# HEBoard_ver4.net
KiCad netlist of a schematic drawn in Altium Designer
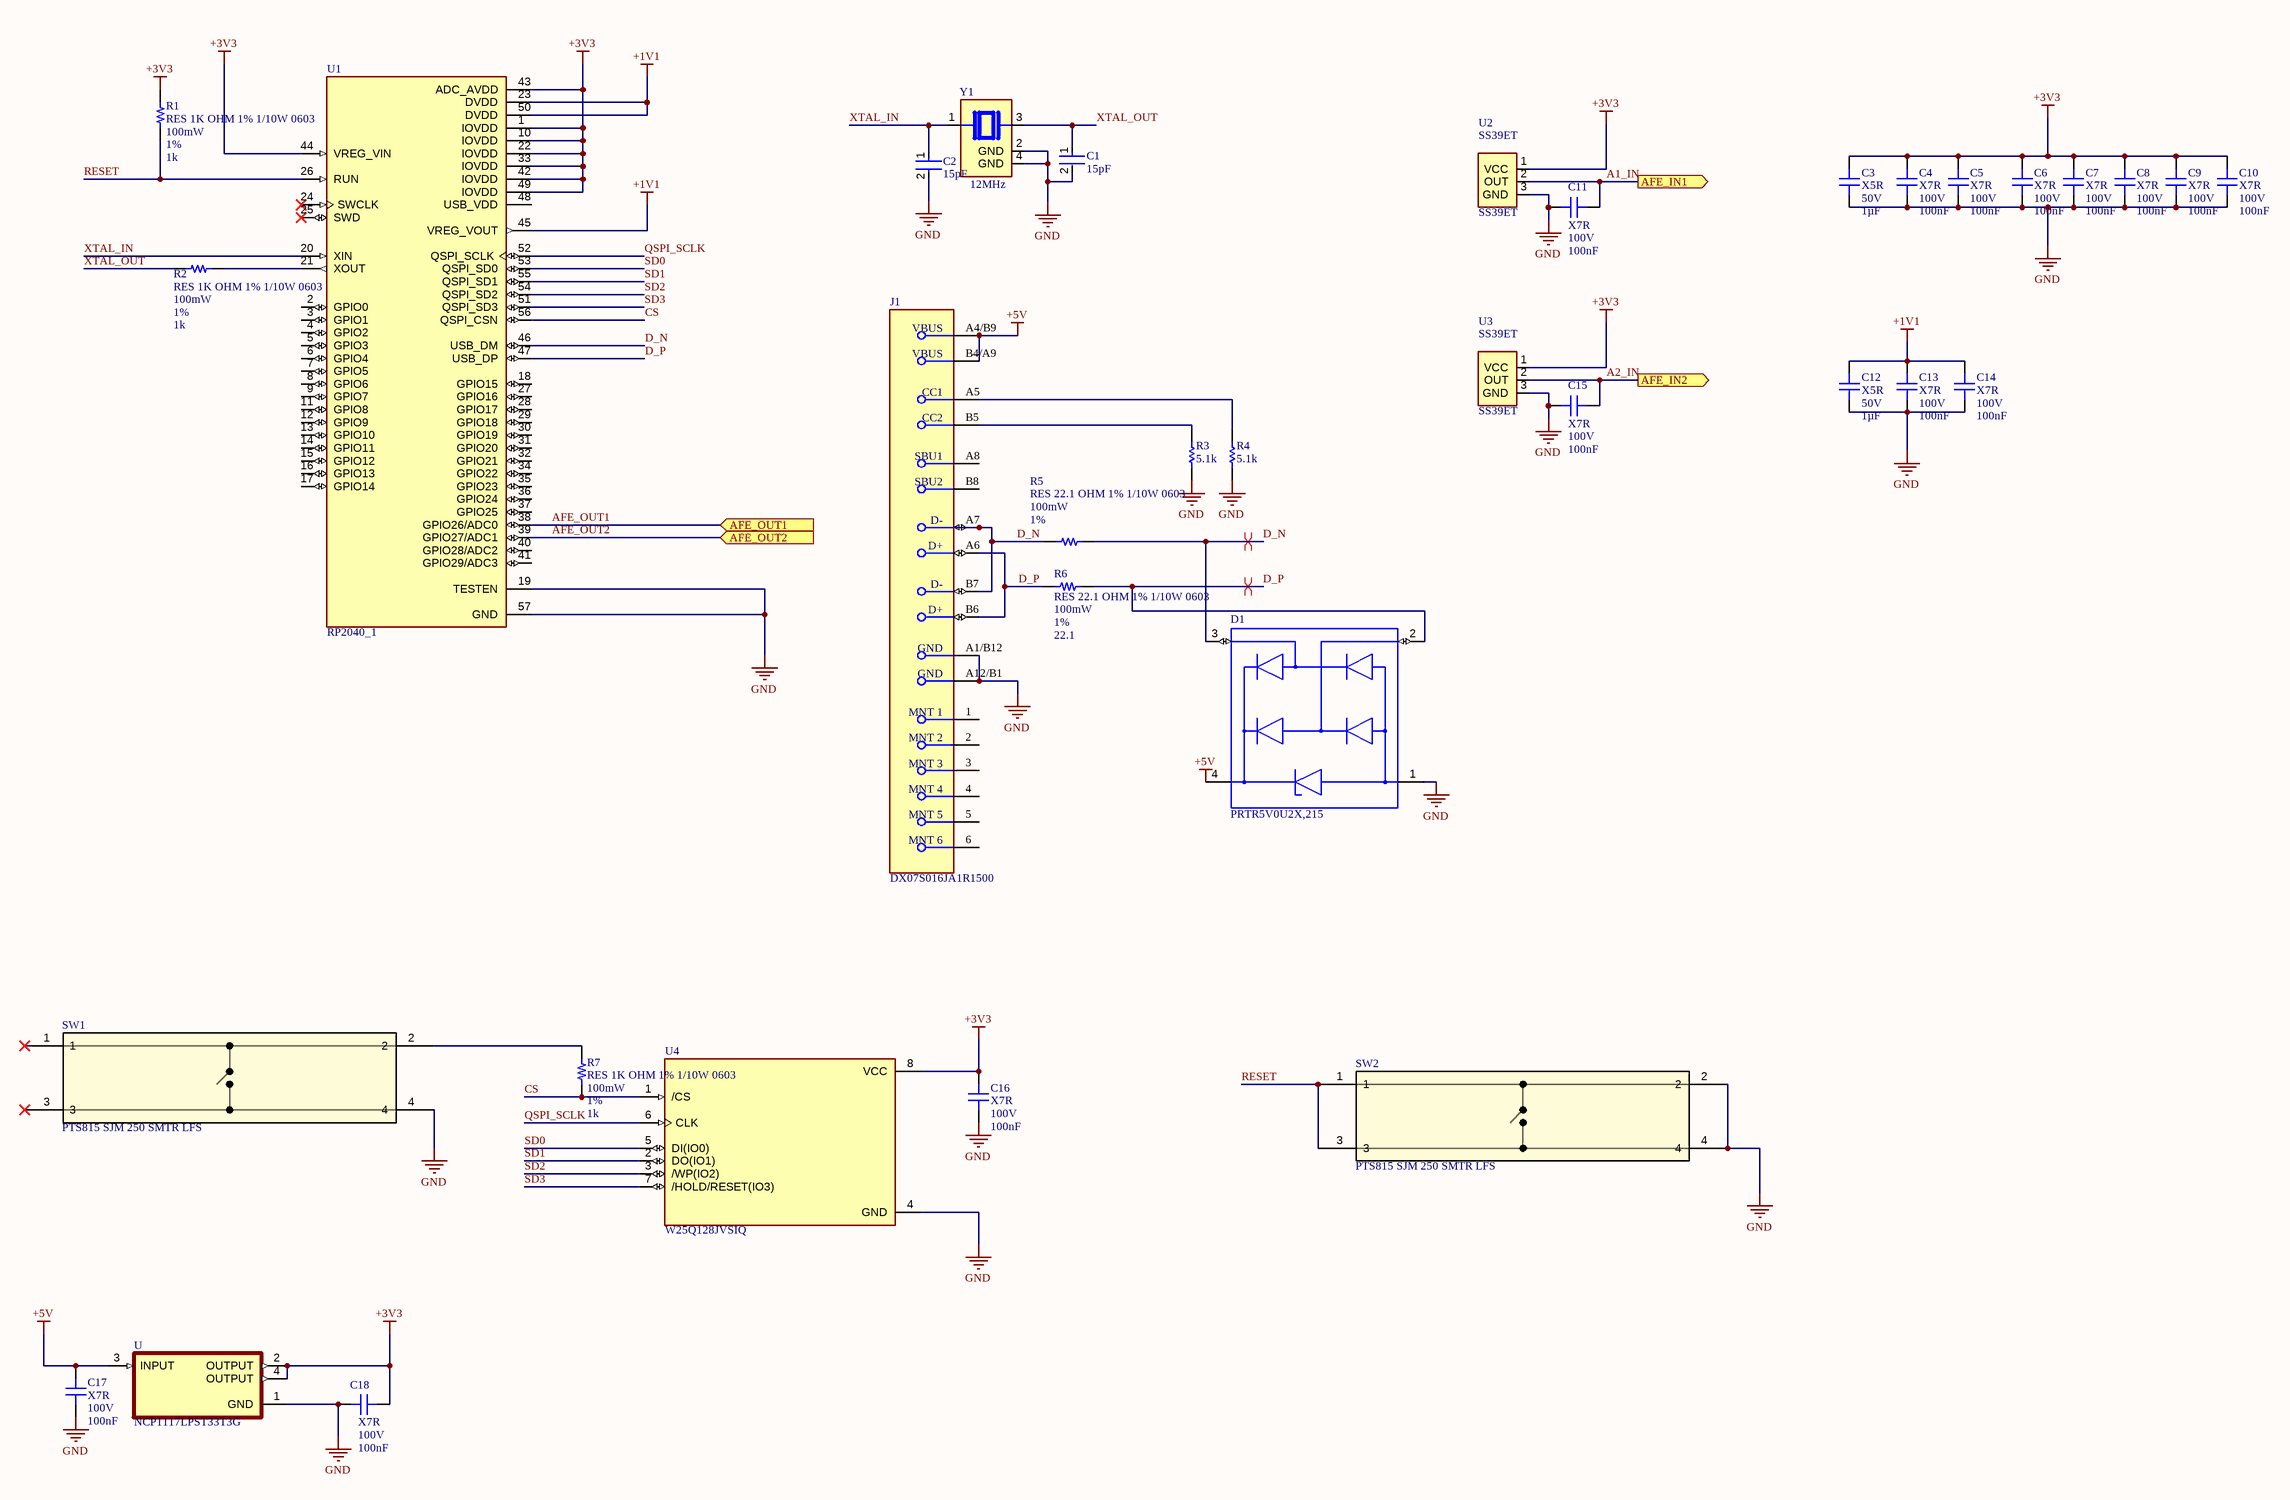
[diagram p0: HEBoard_ver4.SchDoc]

(export (version "E")
  (design (tool "Eeschema 10.0.6"))
  (components
    (comp (ref "C1")
      (value "15pF")
      (footprint "FP-CC0603-0_9-MFG")
      (description "CAP CER 15PF 50V C0G/NPO 0603")
      (fields (field (name "TOLERANCE") "5%"))
      (libsource (lib "Altium Content Vault") (part "11868f565c42a9108669ba33697ecf6"))
    )
    (comp (ref "C2")
      (value "15pF")
      (footprint "FP-CC0603-0_9-MFG")
      (description "CAP CER 15PF 50V C0G/NPO 0603")
      (fields (field (name "TOLERANCE") "5%"))
      (libsource (lib "Altium Content Vault") (part "11868f565c42a9108669ba33697ecf6"))
    )
    (comp (ref "C3")
      (value "CAP CER 1UF 50V X5R 0603")
      (footprint "CAP 0603_1608")
      (description "1µF ±10% 50V Ceramic Capacitor X7R 0603 (1608 Metric)")
      (fields
        (field (name "DIELECTRIC CODE") "X5R")
        (field (name "VOLTAGE RATING") "50V")
        (field (name "CAPACITANCE") "1µF")
        (field (name "TOLERANCE") "10%")
      )
      (libsource (lib "Midnight Sun") (part "Capacitor"))
    )
    (comp (ref "C4")
      (value "CAP CER 0.1UF 100V 10% X7R 0603")
      (footprint "CAP 0603_1608")
      (fields
        (field (name "DIELECTRIC CODE") "X7R")
        (field (name "VOLTAGE RATING") "100V")
        (field (name "CAPACITANCE") "100nF")
        (field (name "TOLERANCE") "10%")
      )
      (libsource (lib "Midnight Sun") (part "Capacitor"))
    )
    (comp (ref "C5")
      (value "CAP CER 0.1UF 100V 10% X7R 0603")
      (footprint "CAP 0603_1608")
      (fields
        (field (name "DIELECTRIC CODE") "X7R")
        (field (name "VOLTAGE RATING") "100V")
        (field (name "CAPACITANCE") "100nF")
        (field (name "TOLERANCE") "10%")
      )
      (libsource (lib "Midnight Sun") (part "Capacitor"))
    )
    (comp (ref "C6")
      (value "CAP CER 0.1UF 100V 10% X7R 0603")
      (footprint "CAP 0603_1608")
      (fields
        (field (name "DIELECTRIC CODE") "X7R")
        (field (name "VOLTAGE RATING") "100V")
        (field (name "CAPACITANCE") "100nF")
        (field (name "TOLERANCE") "10%")
      )
      (libsource (lib "Midnight Sun") (part "Capacitor"))
    )
    (comp (ref "C7")
      (value "CAP CER 0.1UF 100V 10% X7R 0603")
      (footprint "CAP 0603_1608")
      (fields
        (field (name "DIELECTRIC CODE") "X7R")
        (field (name "VOLTAGE RATING") "100V")
        (field (name "CAPACITANCE") "100nF")
        (field (name "TOLERANCE") "10%")
      )
      (libsource (lib "Midnight Sun") (part "Capacitor"))
    )
    (comp (ref "C8")
      (value "CAP CER 0.1UF 100V 10% X7R 0603")
      (footprint "CAP 0603_1608")
      (fields
        (field (name "DIELECTRIC CODE") "X7R")
        (field (name "VOLTAGE RATING") "100V")
        (field (name "CAPACITANCE") "100nF")
        (field (name "TOLERANCE") "10%")
      )
      (libsource (lib "Midnight Sun") (part "Capacitor"))
    )
    (comp (ref "C9")
      (value "CAP CER 0.1UF 100V 10% X7R 0603")
      (footprint "CAP 0603_1608")
      (fields
        (field (name "DIELECTRIC CODE") "X7R")
        (field (name "VOLTAGE RATING") "100V")
        (field (name "CAPACITANCE") "100nF")
        (field (name "TOLERANCE") "10%")
      )
      (libsource (lib "Midnight Sun") (part "Capacitor"))
    )
    (comp (ref "C10")
      (value "CAP CER 0.1UF 100V 10% X7R 0603")
      (footprint "CAP 0603_1608")
      (fields
        (field (name "DIELECTRIC CODE") "X7R")
        (field (name "VOLTAGE RATING") "100V")
        (field (name "CAPACITANCE") "100nF")
        (field (name "TOLERANCE") "10%")
      )
      (libsource (lib "Midnight Sun") (part "Capacitor"))
    )
    (comp (ref "C11")
      (value "CAP CER 0.1UF 100V 10% X7R 0603")
      (footprint "CAP 0603_1608")
      (fields
        (field (name "DIELECTRIC CODE") "X7R")
        (field (name "VOLTAGE RATING") "100V")
        (field (name "CAPACITANCE") "100nF")
        (field (name "TOLERANCE") "10%")
      )
      (libsource (lib "Midnight Sun") (part "Capacitor"))
    )
    (comp (ref "C12")
      (value "CAP CER 1UF 50V X5R 0603")
      (footprint "CAP 0603_1608")
      (description "1µF ±10% 50V Ceramic Capacitor X7R 0603 (1608 Metric)")
      (fields
        (field (name "DIELECTRIC CODE") "X5R")
        (field (name "VOLTAGE RATING") "50V")
        (field (name "CAPACITANCE") "1µF")
        (field (name "TOLERANCE") "10%")
      )
      (libsource (lib "Midnight Sun") (part "Capacitor"))
    )
    (comp (ref "C13")
      (value "CAP CER 0.1UF 100V 10% X7R 0603")
      (footprint "CAP 0603_1608")
      (fields
        (field (name "DIELECTRIC CODE") "X7R")
        (field (name "VOLTAGE RATING") "100V")
        (field (name "CAPACITANCE") "100nF")
        (field (name "TOLERANCE") "10%")
      )
      (libsource (lib "Midnight Sun") (part "Capacitor"))
    )
    (comp (ref "C14")
      (value "CAP CER 0.1UF 100V 10% X7R 0603")
      (footprint "CAP 0603_1608")
      (fields
        (field (name "DIELECTRIC CODE") "X7R")
        (field (name "VOLTAGE RATING") "100V")
        (field (name "CAPACITANCE") "100nF")
        (field (name "TOLERANCE") "10%")
      )
      (libsource (lib "Midnight Sun") (part "Capacitor"))
    )
    (comp (ref "C15")
      (value "CAP CER 0.1UF 100V 10% X7R 0603")
      (footprint "CAP 0603_1608")
      (fields
        (field (name "DIELECTRIC CODE") "X7R")
        (field (name "VOLTAGE RATING") "100V")
        (field (name "CAPACITANCE") "100nF")
        (field (name "TOLERANCE") "10%")
      )
      (libsource (lib "Midnight Sun") (part "Capacitor"))
    )
    (comp (ref "C16")
      (value "CAP CER 0.1UF 100V 10% X7R 0603")
      (footprint "CAP 0603_1608")
      (fields
        (field (name "DIELECTRIC CODE") "X7R")
        (field (name "VOLTAGE RATING") "100V")
        (field (name "CAPACITANCE") "100nF")
        (field (name "TOLERANCE") "10%")
      )
      (libsource (lib "Midnight Sun") (part "Capacitor"))
    )
    (comp (ref "C17")
      (value "CAP CER 0.1UF 100V 10% X7R 0603")
      (footprint "CAP 0603_1608")
      (fields
        (field (name "DIELECTRIC CODE") "X7R")
        (field (name "VOLTAGE RATING") "100V")
        (field (name "CAPACITANCE") "100nF")
        (field (name "TOLERANCE") "10%")
      )
      (libsource (lib "Midnight Sun") (part "Capacitor"))
    )
    (comp (ref "C18")
      (value "CAP CER 0.1UF 100V 10% X7R 0603")
      (footprint "CAP 0603_1608")
      (fields
        (field (name "DIELECTRIC CODE") "X7R")
        (field (name "VOLTAGE RATING") "100V")
        (field (name "CAPACITANCE") "100nF")
        (field (name "TOLERANCE") "10%")
      )
      (libsource (lib "Midnight Sun") (part "Capacitor"))
    )
    (comp (ref "D1")
      (value "PRTR5V0U2X,215")
      (footprint "FP-SOT143B-MFG")
      (description "TVS DIODE 5.5V SOT143B")
      (libsource (lib "Altium Content Vault") (part "31e4fa1655694efd507c8a671e666ef"))
    )
    (comp (ref "J1")
      (value "DX07S016JA1R1500")
      (footprint "FP-DX07S016JA1R1500-MFG")
      (description "CONN RCP USB2.0 TYP C 24P SMD RA")
      (libsource (lib "Altium Content Vault") (part "7f3e9989102a0f22bff9cb010881d34"))
    )
    (comp (ref "R1")
      (value "RES 1K OHM 1% 1/10W 0603")
      (footprint "RES 0603_1608")
      (description "1 kOhms ±1% 0.1W, 1/10W Chip Resistor 0603 (1608 Metric) Moisture Resistant Thick Film")
      (fields
        (field (name "POWER RATING") "100mW")
        (field (name "TOLERANCE") "1%")
        (field (name "RESISTANCE") "1k")
      )
      (libsource (lib "Midnight Sun") (part "Resistor"))
    )
    (comp (ref "R2")
      (value "RES 1K OHM 1% 1/10W 0603")
      (footprint "RES 0603_1608")
      (description "1 kOhms ±1% 0.1W, 1/10W Chip Resistor 0603 (1608 Metric) Moisture Resistant Thick Film")
      (fields
        (field (name "POWER RATING") "100mW")
        (field (name "TOLERANCE") "1%")
        (field (name "RESISTANCE") "1k")
      )
      (libsource (lib "Midnight Sun") (part "Resistor"))
    )
    (comp (ref "R3")
      (value "5.1k")
      (footprint "RESC1005X40X25NL05T10")
      (fields (field (name "PART NUMBER") "RC0402FR-075K1L") (field (name "MANUFACTURER") "Yageo / Phycomp"))
      (libsource (lib "Altium Content Vault") (part "RES"))
    )
    (comp (ref "R4")
      (value "5.1k")
      (footprint "RESC1005X40X25NL05T10")
      (fields (field (name "PART NUMBER") "RC0402FR-075K1L") (field (name "MANUFACTURER") "Yageo / Phycomp"))
      (libsource (lib "Altium Content Vault") (part "RES"))
    )
    (comp (ref "R5")
      (value "RES 22.1 OHM 1% 1/10W 0603")
      (footprint "RES 0603_1608")
      (fields (field (name "POWER RATING") "100mW") (field (name "TOLERANCE") "1%"))
      (libsource (lib "Midnight Sun") (part "Resistor"))
    )
    (comp (ref "R6")
      (value "RES 22.1 OHM 1% 1/10W 0603")
      (footprint "RES 0603_1608")
      (fields
        (field (name "POWER RATING") "100mW")
        (field (name "TOLERANCE") "1%")
        (field (name "RESISTANCE") "22.1")
      )
      (libsource (lib "Midnight Sun") (part "Resistor"))
    )
    (comp (ref "R7")
      (value "RES 1K OHM 1% 1/10W 0603")
      (footprint "RES 0603_1608")
      (description "1 kOhms ±1% 0.1W, 1/10W Chip Resistor 0603 (1608 Metric) Moisture Resistant Thick Film")
      (fields
        (field (name "POWER RATING") "100mW")
        (field (name "TOLERANCE") "1%")
        (field (name "RESISTANCE") "1k")
      )
      (libsource (lib "Midnight Sun") (part "Resistor"))
    )
    (comp (ref "SW1")
      (value "PTS815 SJM 250 SMTR LFS")
      (footprint "SW4_PTS815 SJM 250 SMTR LFS_CNK")
      (description "No Description Available")
      (libsource (lib "HEBoard_ver4") (part "PTS815 SJM 250 SMTR LFS"))
    )
    (comp (ref "SW2")
      (value "PTS815 SJM 250 SMTR LFS")
      (footprint "SW4_PTS815 SJM 250 SMTR LFS_CNK")
      (description "No Description Available")
      (libsource (lib "HEBoard_ver4") (part "PTS815 SJM 250 SMTR LFS"))
    )
    (comp (ref "U")
      (value "NCP1117LPST33T3G")
      (footprint "SnapEDApcb:SOT230P700X175-4N")
      (description "Linear Voltage Regulator IC 1 Output 1A SOT-223")
      (fields (field (name "MF") "ON Semiconductor"))
      (libsource (lib "HEBoard_ver4") (part "NCP1117LPST33T3G"))
    )
    (comp (ref "U1")
      (value "RP2040_1")
      (footprint "QFN40P700X700X90-57N")
      (description "RP2040 chip for Raspberry Pi Pico - ARMÂ® CortexÂ®-M0+ MCU 32-Bit")
      (fields (field (name "MP") "RP2040") (field (name "MF") "Raspberry Pi"))
      (libsource (lib "HEBoard_ver4") (part "RP2040_1"))
    )
    (comp (ref "U2")
      (value "SS39ET")
      (footprint "CHRY-MX1A-11NW_V")
      (description "analog Hall Effect Sensor 1.5 mA 2.7 - 6.5 V dc ¦ Honeywell SS39ET")
      (fields (field (name "MF") "Honeywell Sensing and Productivity Solutions"))
      (libsource (lib "HEBoard_ver4") (part "SS39ET"))
    )
    (comp (ref "U3")
      (value "SS39ET")
      (footprint "CHRY-MX1A-11NW_V")
      (description "analog Hall Effect Sensor 1.5 mA 2.7 - 6.5 V dc ¦ Honeywell SS39ET")
      (fields (field (name "MF") "Honeywell Sensing and Productivity Solutions"))
      (libsource (lib "HEBoard_ver4") (part "SS39ET"))
    )
    (comp (ref "U4")
      (value "W25Q128JVSIQ")
      (footprint "SOIC127P790X216-8N:SOIC127P790X216-8N")
      (description "FLASH - NOR Memory IC 128Mb (16M x 8) SPI - Quad I/O, QPI, DTR 133 MHz 8-SOIC")
      (fields (field (name "MF") "Winbond Electronics"))
      (libsource (lib "HEBoard_ver4") (part "W25Q128JVSIQ"))
    )
    (comp (ref "Y1")
      (value "12MHz")
      (footprint "XTAL_ABM8G-12.000MHZ-4Y-T3")
      (description "12 MHz Â±30ppm Crystal 10pF 120 Ohms 4-SMD, No Lead")
      (fields (field (name "MF") "Abracon") (field (name "MP") "ABM8G-12.000MHZ-4Y-T3"))
      (libsource (lib "HEBoard_ver4") (part "ABM8G-12.000MHZ-4Y-T3"))
    )
  )
  (nets
    (net (code "1") (name "+1V1") (class "Default")
      (node (ref "C12") (pin "2") (pinfunction "2_2") (pintype "passive"))
      (node (ref "C13") (pin "2") (pinfunction "2_2") (pintype "passive"))
      (node (ref "C14") (pin "2") (pinfunction "2_2") (pintype "passive"))
      (node (ref "U1") (pin "23") (pinfunction "DVDD_23") (pintype "power_in"))
      (node (ref "U1") (pin "45") (pinfunction "VREG_VOUT_45") (pintype "output"))
      (node (ref "U1") (pin "50") (pinfunction "DVDD_50") (pintype "power_in"))
    )
    (net (code "2") (name "+3V3") (class "Default")
      (node (ref "C10") (pin "2") (pinfunction "2_2") (pintype "passive"))
      (node (ref "C16") (pin "2") (pinfunction "2_2") (pintype "passive"))
      (node (ref "C18") (pin "1") (pinfunction "1_1") (pintype "passive"))
      (node (ref "C3") (pin "2") (pinfunction "2_2") (pintype "passive"))
      (node (ref "C4") (pin "2") (pinfunction "2_2") (pintype "passive"))
      (node (ref "C5") (pin "2") (pinfunction "2_2") (pintype "passive"))
      (node (ref "C6") (pin "2") (pinfunction "2_2") (pintype "passive"))
      (node (ref "C7") (pin "2") (pinfunction "2_2") (pintype "passive"))
      (node (ref "C8") (pin "2") (pinfunction "2_2") (pintype "passive"))
      (node (ref "C9") (pin "2") (pinfunction "2_2") (pintype "passive"))
      (node (ref "R1") (pin "2") (pinfunction "2_2") (pintype "passive"))
      (node (ref "U") (pin "2") (pinfunction "OUTPUT_2") (pintype "output"))
      (node (ref "U") (pin "4") (pinfunction "OUTPUT_4") (pintype "output"))
      (node (ref "U1") (pin "1") (pinfunction "IOVDD_1") (pintype "power_in"))
      (node (ref "U1") (pin "10") (pinfunction "IOVDD_10") (pintype "power_in"))
      (node (ref "U1") (pin "22") (pinfunction "IOVDD_22") (pintype "power_in"))
      (node (ref "U1") (pin "33") (pinfunction "IOVDD_33") (pintype "power_in"))
      (node (ref "U1") (pin "42") (pinfunction "IOVDD_42") (pintype "power_in"))
      (node (ref "U1") (pin "43") (pinfunction "ADC_AVDD_43") (pintype "power_in"))
      (node (ref "U1") (pin "44") (pinfunction "VREG_VIN_44") (pintype "input"))
      (node (ref "U1") (pin "49") (pinfunction "IOVDD_49") (pintype "power_in"))
      (node (ref "U2") (pin "1") (pinfunction "VCC_1") (pintype "passive"))
      (node (ref "U3") (pin "1") (pinfunction "VCC_1") (pintype "passive"))
      (node (ref "U4") (pin "8") (pinfunction "VCC_8") (pintype "power_in"))
    )
    (net (code "3") (name "+5V") (class "Default")
      (node (ref "C17") (pin "2") (pinfunction "2_2") (pintype "passive"))
      (node (ref "D1") (pin "4") (pinfunction "VCC_4") (pintype "power_in"))
      (node (ref "J1") (pin "A4/B9") (pinfunction "VBUS_A4/B9") (pintype "power_in"))
      (node (ref "J1") (pin "B4/A9") (pinfunction "VBUS_B4/A9") (pintype "power_in"))
      (node (ref "U") (pin "3") (pinfunction "INPUT_3") (pintype "input"))
    )
    (net (code "4") (name "/A1_IN") (class "Default")
      (node (ref "C11") (pin "1") (pinfunction "1_1") (pintype "passive"))
      (node (ref "U2") (pin "2") (pinfunction "OUT_2") (pintype "passive"))
    )
    (net (code "5") (name "/A2_IN") (class "Default")
      (node (ref "C15") (pin "1") (pinfunction "1_1") (pintype "passive"))
      (node (ref "U3") (pin "2") (pinfunction "OUT_2") (pintype "passive"))
    )
    (net (code "6") (name "/AFE_OUT1") (class "Default")
      (node (ref "U1") (pin "38") (pinfunction "GPIO26/ADC0_38") (pintype "bidirectional"))
    )
    (net (code "7") (name "/AFE_OUT2") (class "Default")
      (node (ref "U1") (pin "39") (pinfunction "GPIO27/ADC1_39") (pintype "bidirectional"))
    )
    (net (code "8") (name "/CS") (class "Default")
      (node (ref "R7") (pin "2") (pinfunction "2_2") (pintype "passive"))
      (node (ref "U1") (pin "56") (pinfunction "QSPI_CSN_56") (pintype "bidirectional"))
      (node (ref "U4") (pin "1") (pinfunction "/CS_1") (pintype "input"))
    )
    (net (code "9") (name "/D_N") (class "Default")
      (node (ref "D1") (pin "3") (pinfunction "I/O_2_3") (pintype "bidirectional"))
      (node (ref "J1") (pin "A7") (pinfunction "D-_A7") (pintype "bidirectional"))
      (node (ref "J1") (pin "B7") (pinfunction "D-_B7") (pintype "bidirectional"))
      (node (ref "R5") (pin "1") (pinfunction "1_1") (pintype "passive"))
      (node (ref "R5") (pin "2") (pinfunction "2_2") (pintype "passive"))
      (node (ref "U1") (pin "46") (pinfunction "USB_DM_46") (pintype "bidirectional"))
    )
    (net (code "10") (name "/D_P") (class "Default")
      (node (ref "D1") (pin "2") (pinfunction "I/O_1_2") (pintype "bidirectional"))
      (node (ref "J1") (pin "A6") (pinfunction "D+_A6") (pintype "bidirectional"))
      (node (ref "J1") (pin "B6") (pinfunction "D+_B6") (pintype "bidirectional"))
      (node (ref "R6") (pin "1") (pinfunction "1_1") (pintype "passive"))
      (node (ref "R6") (pin "2") (pinfunction "2_2") (pintype "passive"))
      (node (ref "U1") (pin "47") (pinfunction "USB_DP_47") (pintype "bidirectional"))
    )
    (net (code "11") (name "/QSPI_SCLK") (class "Default")
      (node (ref "U1") (pin "52") (pinfunction "QSPI_SCLK_52") (pintype "bidirectional"))
      (node (ref "U4") (pin "6") (pinfunction "CLK_6") (pintype "input"))
    )
    (net (code "12") (name "/RESET") (class "Default")
      (node (ref "R1") (pin "1") (pinfunction "1_1") (pintype "passive"))
      (node (ref "SW2") (pin "1") (pinfunction "1_1") (pintype "passive"))
      (node (ref "SW2") (pin "3") (pinfunction "3_3") (pintype "passive"))
      (node (ref "U1") (pin "26") (pinfunction "RUN_26") (pintype "input"))
    )
    (net (code "13") (name "/SD0") (class "Default")
      (node (ref "U1") (pin "53") (pinfunction "QSPI_SD0_53") (pintype "bidirectional"))
      (node (ref "U4") (pin "5") (pinfunction "DI(IO0)_5") (pintype "bidirectional"))
    )
    (net (code "14") (name "/SD1") (class "Default")
      (node (ref "U1") (pin "55") (pinfunction "QSPI_SD1_55") (pintype "bidirectional"))
      (node (ref "U4") (pin "2") (pinfunction "DO(IO1)_2") (pintype "bidirectional"))
    )
    (net (code "15") (name "/SD2") (class "Default")
      (node (ref "U1") (pin "54") (pinfunction "QSPI_SD2_54") (pintype "bidirectional"))
      (node (ref "U4") (pin "3") (pinfunction "/WP(IO2)_3") (pintype "bidirectional"))
    )
    (net (code "16") (name "/SD3") (class "Default")
      (node (ref "U1") (pin "51") (pinfunction "QSPI_SD3_51") (pintype "bidirectional"))
      (node (ref "U4") (pin "7") (pinfunction "/HOLD/RESET(IO3)_7") (pintype "bidirectional"))
    )
    (net (code "17") (name "/XTAL_IN") (class "Default")
      (node (ref "C2") (pin "1") (pinfunction "1_1") (pintype "passive"))
      (node (ref "U1") (pin "20") (pinfunction "XIN_20") (pintype "input"))
      (node (ref "Y1") (pin "1") (pinfunction "1_1") (pintype "passive"))
    )
    (net (code "18") (name "/XTAL_OUT") (class "Default")
      (node (ref "C1") (pin "1") (pinfunction "1_1") (pintype "passive"))
      (node (ref "R2") (pin "2") (pinfunction "2_2") (pintype "passive"))
      (node (ref "Y1") (pin "3") (pinfunction "2_3") (pintype "passive"))
    )
    (net (code "19") (name "GND") (class "Default")
      (node (ref "C1") (pin "2") (pinfunction "2_2") (pintype "passive"))
      (node (ref "C10") (pin "1") (pinfunction "1_1") (pintype "passive"))
      (node (ref "C11") (pin "2") (pinfunction "2_2") (pintype "passive"))
      (node (ref "C12") (pin "1") (pinfunction "1_1") (pintype "passive"))
      (node (ref "C13") (pin "1") (pinfunction "1_1") (pintype "passive"))
      (node (ref "C14") (pin "1") (pinfunction "1_1") (pintype "passive"))
      (node (ref "C15") (pin "2") (pinfunction "2_2") (pintype "passive"))
      (node (ref "C16") (pin "1") (pinfunction "1_1") (pintype "passive"))
      (node (ref "C17") (pin "1") (pinfunction "1_1") (pintype "passive"))
      (node (ref "C18") (pin "2") (pinfunction "2_2") (pintype "passive"))
      (node (ref "C2") (pin "2") (pinfunction "2_2") (pintype "passive"))
      (node (ref "C3") (pin "1") (pinfunction "1_1") (pintype "passive"))
      (node (ref "C4") (pin "1") (pinfunction "1_1") (pintype "passive"))
      (node (ref "C5") (pin "1") (pinfunction "1_1") (pintype "passive"))
      (node (ref "C6") (pin "1") (pinfunction "1_1") (pintype "passive"))
      (node (ref "C7") (pin "1") (pinfunction "1_1") (pintype "passive"))
      (node (ref "C8") (pin "1") (pinfunction "1_1") (pintype "passive"))
      (node (ref "C9") (pin "1") (pinfunction "1_1") (pintype "passive"))
      (node (ref "D1") (pin "1") (pinfunction "GND_1") (pintype "power_in"))
      (node (ref "J1") (pin "A1/B12") (pinfunction "GND_A1/B12") (pintype "power_in"))
      (node (ref "J1") (pin "A12/B1") (pinfunction "GND_A12/B1") (pintype "power_in"))
      (node (ref "R3") (pin "1") (pinfunction "1_1") (pintype "passive"))
      (node (ref "R4") (pin "1") (pinfunction "1_1") (pintype "passive"))
      (node (ref "SW1") (pin "4") (pinfunction "4_4") (pintype "passive"))
      (node (ref "SW2") (pin "2") (pinfunction "2_2") (pintype "passive"))
      (node (ref "SW2") (pin "4") (pinfunction "4_4") (pintype "passive"))
      (node (ref "U") (pin "1") (pinfunction "GND_1") (pintype "power_in"))
      (node (ref "U1") (pin "19") (pinfunction "TESTEN_19") (pintype "passive"))
      (node (ref "U1") (pin "57") (pinfunction "GND_57") (pintype "power_in"))
      (node (ref "U2") (pin "3") (pinfunction "GND_3") (pintype "passive"))
      (node (ref "U3") (pin "3") (pinfunction "GND_3") (pintype "passive"))
      (node (ref "U4") (pin "4") (pinfunction "GND_4") (pintype "power_in"))
      (node (ref "Y1") (pin "2") (pinfunction "GND_2") (pintype "power_in"))
      (node (ref "Y1") (pin "4") (pinfunction "GND_4") (pintype "power_in"))
    )
    (net (code "20") (name "Net-(J1-CC1)") (class "Default")
      (node (ref "J1") (pin "A5") (pinfunction "CC1_A5") (pintype "passive"))
      (node (ref "R4") (pin "2") (pinfunction "2_2") (pintype "passive"))
    )
    (net (code "21") (name "Net-(J1-CC2)") (class "Default")
      (node (ref "J1") (pin "B5") (pinfunction "CC2_B5") (pintype "passive"))
      (node (ref "R3") (pin "2") (pinfunction "2_2") (pintype "passive"))
    )
    (net (code "22") (name "Net-(R7-Pad1)") (class "Default")
      (node (ref "R7") (pin "1") (pinfunction "1_1") (pintype "passive"))
      (node (ref "SW1") (pin "2") (pinfunction "2_2") (pintype "passive"))
    )
    (net (code "23") (name "Net-(U1-XOUT)") (class "Default")
      (node (ref "R2") (pin "1") (pinfunction "1_1") (pintype "passive"))
      (node (ref "U1") (pin "21") (pinfunction "XOUT_21") (pintype "output"))
    )
    (net (code "24") (name "unconnected-(J1-MNT_1-Pad1)") (class "Default")
      (node (ref "J1") (pin "1") (pinfunction "MNT_1_1") (pintype "passive"))
    )
    (net (code "25") (name "unconnected-(J1-MNT_2-Pad2)") (class "Default")
      (node (ref "J1") (pin "2") (pinfunction "MNT_2_2") (pintype "passive"))
    )
    (net (code "26") (name "unconnected-(J1-MNT_3-Pad3)") (class "Default")
      (node (ref "J1") (pin "3") (pinfunction "MNT_3_3") (pintype "passive"))
    )
    (net (code "27") (name "unconnected-(J1-MNT_4-Pad4)") (class "Default")
      (node (ref "J1") (pin "4") (pinfunction "MNT_4_4") (pintype "passive"))
    )
    (net (code "28") (name "unconnected-(J1-MNT_5-Pad5)") (class "Default")
      (node (ref "J1") (pin "5") (pinfunction "MNT_5_5") (pintype "passive"))
    )
    (net (code "29") (name "unconnected-(J1-MNT_6-Pad6)") (class "Default")
      (node (ref "J1") (pin "6") (pinfunction "MNT_6_6") (pintype "passive"))
    )
    (net (code "30") (name "unconnected-(J1-SBU1-PadA8)") (class "Default")
      (node (ref "J1") (pin "A8") (pinfunction "SBU1_A8") (pintype "passive"))
    )
    (net (code "31") (name "unconnected-(J1-SBU2-PadB8)") (class "Default")
      (node (ref "J1") (pin "B8") (pinfunction "SBU2_B8") (pintype "passive"))
    )
    (net (code "32") (name "unconnected-(SW1-Pad1)") (class "Default")
      (node (ref "SW1") (pin "1") (pinfunction "1_1") (pintype "passive+no_connect"))
    )
    (net (code "33") (name "unconnected-(SW1-Pad3)") (class "Default")
      (node (ref "SW1") (pin "3") (pinfunction "3_3") (pintype "passive+no_connect"))
    )
    (net (code "34") (name "unconnected-(U1-GPIO0-Pad2)") (class "Default")
      (node (ref "U1") (pin "2") (pinfunction "GPIO0_2") (pintype "bidirectional"))
    )
    (net (code "35") (name "unconnected-(U1-GPIO1-Pad3)") (class "Default")
      (node (ref "U1") (pin "3") (pinfunction "GPIO1_3") (pintype "bidirectional"))
    )
    (net (code "36") (name "unconnected-(U1-GPIO2-Pad4)") (class "Default")
      (node (ref "U1") (pin "4") (pinfunction "GPIO2_4") (pintype "bidirectional"))
    )
    (net (code "37") (name "unconnected-(U1-GPIO3-Pad5)") (class "Default")
      (node (ref "U1") (pin "5") (pinfunction "GPIO3_5") (pintype "bidirectional"))
    )
    (net (code "38") (name "unconnected-(U1-GPIO4-Pad6)") (class "Default")
      (node (ref "U1") (pin "6") (pinfunction "GPIO4_6") (pintype "bidirectional"))
    )
    (net (code "39") (name "unconnected-(U1-GPIO5-Pad7)") (class "Default")
      (node (ref "U1") (pin "7") (pinfunction "GPIO5_7") (pintype "bidirectional"))
    )
    (net (code "40") (name "unconnected-(U1-GPIO6-Pad8)") (class "Default")
      (node (ref "U1") (pin "8") (pinfunction "GPIO6_8") (pintype "bidirectional"))
    )
    (net (code "41") (name "unconnected-(U1-GPIO7-Pad9)") (class "Default")
      (node (ref "U1") (pin "9") (pinfunction "GPIO7_9") (pintype "bidirectional"))
    )
    (net (code "42") (name "unconnected-(U1-GPIO8-Pad11)") (class "Default")
      (node (ref "U1") (pin "11") (pinfunction "GPIO8_11") (pintype "bidirectional"))
    )
    (net (code "43") (name "unconnected-(U1-GPIO9-Pad12)") (class "Default")
      (node (ref "U1") (pin "12") (pinfunction "GPIO9_12") (pintype "bidirectional"))
    )
    (net (code "44") (name "unconnected-(U1-GPIO10-Pad13)") (class "Default")
      (node (ref "U1") (pin "13") (pinfunction "GPIO10_13") (pintype "bidirectional"))
    )
    (net (code "45") (name "unconnected-(U1-GPIO11-Pad14)") (class "Default")
      (node (ref "U1") (pin "14") (pinfunction "GPIO11_14") (pintype "bidirectional"))
    )
    (net (code "46") (name "unconnected-(U1-GPIO12-Pad15)") (class "Default")
      (node (ref "U1") (pin "15") (pinfunction "GPIO12_15") (pintype "bidirectional"))
    )
    (net (code "47") (name "unconnected-(U1-GPIO13-Pad16)") (class "Default")
      (node (ref "U1") (pin "16") (pinfunction "GPIO13_16") (pintype "bidirectional"))
    )
    (net (code "48") (name "unconnected-(U1-GPIO14-Pad17)") (class "Default")
      (node (ref "U1") (pin "17") (pinfunction "GPIO14_17") (pintype "bidirectional"))
    )
    (net (code "49") (name "unconnected-(U1-GPIO15-Pad18)") (class "Default")
      (node (ref "U1") (pin "18") (pinfunction "GPIO15_18") (pintype "bidirectional"))
    )
    (net (code "50") (name "unconnected-(U1-GPIO16-Pad27)") (class "Default")
      (node (ref "U1") (pin "27") (pinfunction "GPIO16_27") (pintype "bidirectional"))
    )
    (net (code "51") (name "unconnected-(U1-GPIO17-Pad28)") (class "Default")
      (node (ref "U1") (pin "28") (pinfunction "GPIO17_28") (pintype "bidirectional"))
    )
    (net (code "52") (name "unconnected-(U1-GPIO18-Pad29)") (class "Default")
      (node (ref "U1") (pin "29") (pinfunction "GPIO18_29") (pintype "bidirectional"))
    )
    (net (code "53") (name "unconnected-(U1-GPIO19-Pad30)") (class "Default")
      (node (ref "U1") (pin "30") (pinfunction "GPIO19_30") (pintype "bidirectional"))
    )
    (net (code "54") (name "unconnected-(U1-GPIO20-Pad31)") (class "Default")
      (node (ref "U1") (pin "31") (pinfunction "GPIO20_31") (pintype "bidirectional"))
    )
    (net (code "55") (name "unconnected-(U1-GPIO21-Pad32)") (class "Default")
      (node (ref "U1") (pin "32") (pinfunction "GPIO21_32") (pintype "bidirectional"))
    )
    (net (code "56") (name "unconnected-(U1-GPIO22-Pad34)") (class "Default")
      (node (ref "U1") (pin "34") (pinfunction "GPIO22_34") (pintype "bidirectional"))
    )
    (net (code "57") (name "unconnected-(U1-GPIO23-Pad35)") (class "Default")
      (node (ref "U1") (pin "35") (pinfunction "GPIO23_35") (pintype "bidirectional"))
    )
    (net (code "58") (name "unconnected-(U1-GPIO24-Pad36)") (class "Default")
      (node (ref "U1") (pin "36") (pinfunction "GPIO24_36") (pintype "bidirectional"))
    )
    (net (code "59") (name "unconnected-(U1-GPIO25-Pad37)") (class "Default")
      (node (ref "U1") (pin "37") (pinfunction "GPIO25_37") (pintype "bidirectional"))
    )
    (net (code "60") (name "unconnected-(U1-GPIO28{slash}ADC2-Pad40)") (class "Default")
      (node (ref "U1") (pin "40") (pinfunction "GPIO28/ADC2_40") (pintype "bidirectional"))
    )
    (net (code "61") (name "unconnected-(U1-GPIO29{slash}ADC3-Pad41)") (class "Default")
      (node (ref "U1") (pin "41") (pinfunction "GPIO29/ADC3_41") (pintype "bidirectional"))
    )
    (net (code "62") (name "unconnected-(U1-SWCLK-Pad24)") (class "Default")
      (node (ref "U1") (pin "24") (pinfunction "SWCLK_24") (pintype "input+no_connect"))
    )
    (net (code "63") (name "unconnected-(U1-SWD-Pad25)") (class "Default")
      (node (ref "U1") (pin "25") (pinfunction "SWD_25") (pintype "bidirectional+no_connect"))
    )
    (net (code "64") (name "unconnected-(U1-USB_VDD-Pad48)") (class "Default")
      (node (ref "U1") (pin "48") (pinfunction "USB_VDD_48") (pintype "power_in"))
    )
  )
)
